# OneSLiPoCharger.net
KiCad netlist of a schematic drawn in EAGLE
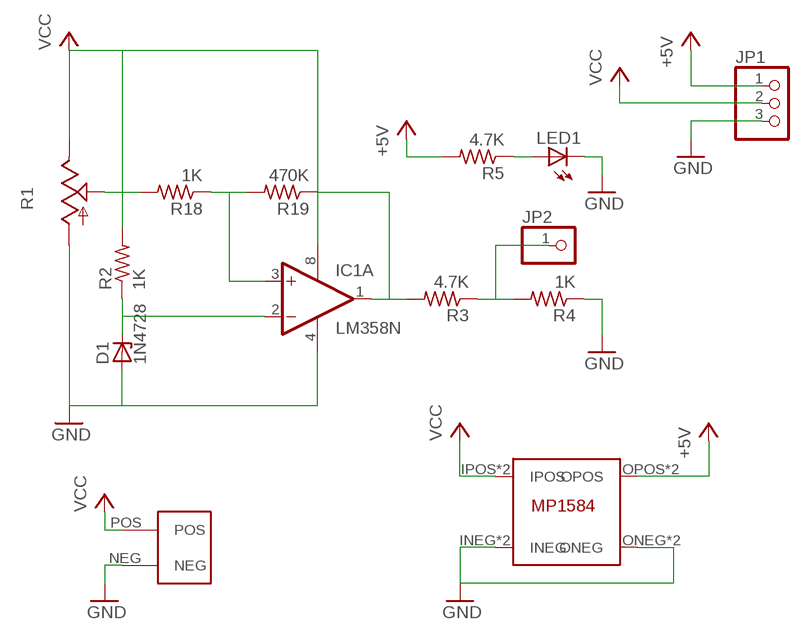
[diagram p0: schematic, sheet 1]
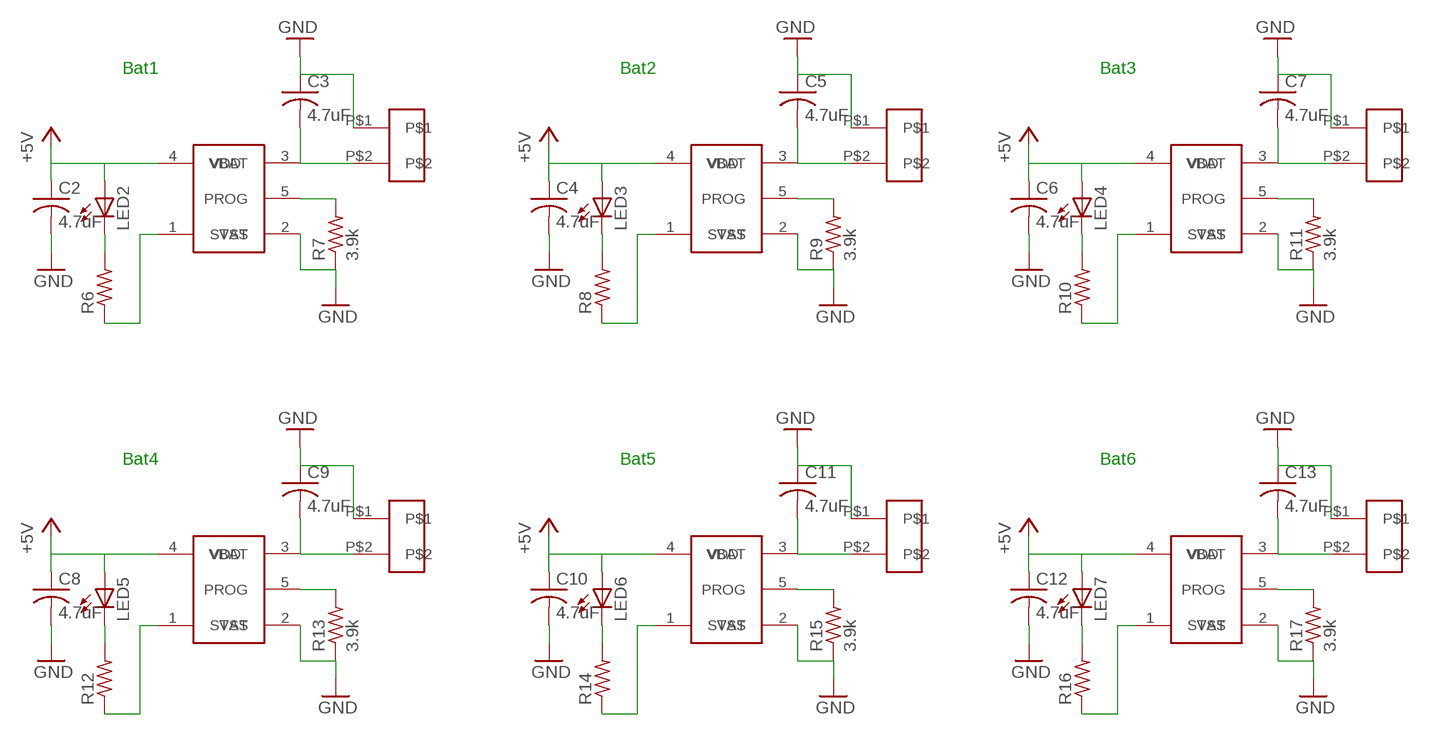
[diagram p1: schematic, sheet 2]

(export (version "E")
  (design (tool "Eeschema 10.0.6"))
  (components
    (comp (ref "D1")
      (value "1N4728")
      (footprint "eagle-import:DO41Z10")
      (libsource (lib "eagle-import") (part "1N4728"))
    )
    (comp (ref "IC1")
      (value "LM358N")
      (footprint "eagle-import:DIL08")
      (libsource (lib "eagle-import") (part "LM358N"))
    )
    (comp (ref "JP1")
      (value "PINHD-1X3")
      (footprint "eagle-import:1X03")
      (libsource (lib "eagle-import") (part "PINHD-1X3"))
    )
    (comp (ref "JP2")
      (value "PINHD-1X1")
      (footprint "eagle-import:1X01")
      (libsource (lib "eagle-import") (part "PINHD-1X1"))
    )
    (comp (ref "LED1")
      (value "LED3MM")
      (footprint "eagle-import:LED3MM")
      (libsource (lib "eagle-import") (part "LED3MM"))
    )
    (comp (ref "R1")
      (value "TRIM_US-B25P")
      (footprint "eagle-import:B25P")
      (libsource (lib "eagle-import") (part "TRIM_US-B25P"))
    )
    (comp (ref "R2")
      (value "1K")
      (footprint "eagle-import:0207_10")
      (libsource (lib "eagle-import") (part "R-US_0207/10"))
    )
    (comp (ref "R3")
      (value "4.7K")
      (footprint "eagle-import:0207_10")
      (libsource (lib "eagle-import") (part "R-US_0207/10"))
    )
    (comp (ref "R4")
      (value "1K")
      (footprint "eagle-import:0207_10")
      (libsource (lib "eagle-import") (part "R-US_0207/10"))
    )
    (comp (ref "R5")
      (value "4.7K")
      (footprint "eagle-import:0207_10")
      (libsource (lib "eagle-import") (part "R-US_0207/10"))
    )
    (comp (ref "R18")
      (value "1K")
      (footprint "eagle-import:0207_10")
      (libsource (lib "eagle-import") (part "R-US_0207/10"))
    )
    (comp (ref "R19")
      (value "470K")
      (footprint "eagle-import:0207_10")
      (libsource (lib "eagle-import") (part "R-US_0207/10"))
    )
    (comp (ref "U$3")
      (value "XT60")
      (footprint "eagle-import:XT60")
      (libsource (lib "eagle-import") (part "XT60"))
    )
    (comp (ref "U$14")
      (value "MP1584EN-MOD")
      (footprint "eagle-import:MP1584MOD-TH")
      (libsource (lib "eagle-import") (part "MP1584EN-MOD"))
    )
    (comp (ref "C2")
      (value "4.7uF")
      (footprint "eagle-import:C0805")
      (libsource (lib "eagle-import") (part "C-USC0805"))
    )
    (comp (ref "C3")
      (value "4.7uF")
      (footprint "eagle-import:C0805")
      (libsource (lib "eagle-import") (part "C-USC0805"))
    )
    (comp (ref "C4")
      (value "4.7uF")
      (footprint "eagle-import:C0805")
      (libsource (lib "eagle-import") (part "C-USC0805"))
    )
    (comp (ref "C5")
      (value "4.7uF")
      (footprint "eagle-import:C0805")
      (libsource (lib "eagle-import") (part "C-USC0805"))
    )
    (comp (ref "C6")
      (value "4.7uF")
      (footprint "eagle-import:C0805")
      (libsource (lib "eagle-import") (part "C-USC0805"))
    )
    (comp (ref "C7")
      (value "4.7uF")
      (footprint "eagle-import:C0805")
      (libsource (lib "eagle-import") (part "C-USC0805"))
    )
    (comp (ref "C8")
      (value "4.7uF")
      (footprint "eagle-import:C0805")
      (libsource (lib "eagle-import") (part "C-USC0805"))
    )
    (comp (ref "C9")
      (value "4.7uF")
      (footprint "eagle-import:C0805")
      (libsource (lib "eagle-import") (part "C-USC0805"))
    )
    (comp (ref "C10")
      (value "4.7uF")
      (footprint "eagle-import:C0805")
      (libsource (lib "eagle-import") (part "C-USC0805"))
    )
    (comp (ref "C11")
      (value "4.7uF")
      (footprint "eagle-import:C0805")
      (libsource (lib "eagle-import") (part "C-USC0805"))
    )
    (comp (ref "C12")
      (value "4.7uF")
      (footprint "eagle-import:C0805")
      (libsource (lib "eagle-import") (part "C-USC0805"))
    )
    (comp (ref "C13")
      (value "4.7uF")
      (footprint "eagle-import:C0805")
      (libsource (lib "eagle-import") (part "C-USC0805"))
    )
    (comp (ref "LED2")
      (value "LED3MM")
      (footprint "eagle-import:LED3MM")
      (libsource (lib "eagle-import") (part "LED3MM"))
    )
    (comp (ref "LED3")
      (value "LED3MM")
      (footprint "eagle-import:LED3MM")
      (libsource (lib "eagle-import") (part "LED3MM"))
    )
    (comp (ref "LED4")
      (value "LED3MM")
      (footprint "eagle-import:LED3MM")
      (libsource (lib "eagle-import") (part "LED3MM"))
    )
    (comp (ref "LED5")
      (value "LED3MM")
      (footprint "eagle-import:LED3MM")
      (libsource (lib "eagle-import") (part "LED3MM"))
    )
    (comp (ref "LED6")
      (value "LED3MM")
      (footprint "eagle-import:LED3MM")
      (libsource (lib "eagle-import") (part "LED3MM"))
    )
    (comp (ref "LED7")
      (value "LED3MM")
      (footprint "eagle-import:LED3MM")
      (libsource (lib "eagle-import") (part "LED3MM"))
    )
    (comp (ref "R6")
      (value "R-US_M0805")
      (footprint "eagle-import:M0805")
      (libsource (lib "eagle-import") (part "R-US_M0805"))
    )
    (comp (ref "R7")
      (value "3.9k")
      (footprint "eagle-import:M0805")
      (libsource (lib "eagle-import") (part "R-US_M0805"))
    )
    (comp (ref "R8")
      (value "R-US_M0805")
      (footprint "eagle-import:M0805")
      (libsource (lib "eagle-import") (part "R-US_M0805"))
    )
    (comp (ref "R9")
      (value "3.9k")
      (footprint "eagle-import:M0805")
      (libsource (lib "eagle-import") (part "R-US_M0805"))
    )
    (comp (ref "R10")
      (value "R-US_M0805")
      (footprint "eagle-import:M0805")
      (libsource (lib "eagle-import") (part "R-US_M0805"))
    )
    (comp (ref "R11")
      (value "3.9k")
      (footprint "eagle-import:M0805")
      (libsource (lib "eagle-import") (part "R-US_M0805"))
    )
    (comp (ref "R12")
      (value "R-US_M0805")
      (footprint "eagle-import:M0805")
      (libsource (lib "eagle-import") (part "R-US_M0805"))
    )
    (comp (ref "R13")
      (value "3.9k")
      (footprint "eagle-import:M0805")
      (libsource (lib "eagle-import") (part "R-US_M0805"))
    )
    (comp (ref "R14")
      (value "R-US_M0805")
      (footprint "eagle-import:M0805")
      (libsource (lib "eagle-import") (part "R-US_M0805"))
    )
    (comp (ref "R15")
      (value "3.9k")
      (footprint "eagle-import:M0805")
      (libsource (lib "eagle-import") (part "R-US_M0805"))
    )
    (comp (ref "R16")
      (value "R-US_M0805")
      (footprint "eagle-import:M0805")
      (libsource (lib "eagle-import") (part "R-US_M0805"))
    )
    (comp (ref "R17")
      (value "3.9k")
      (footprint "eagle-import:M0805")
      (libsource (lib "eagle-import") (part "R-US_M0805"))
    )
    (comp (ref "U$1")
      (value "MCP73831")
      (footprint "eagle-import:MCP73831-SOT23")
      (libsource (lib "eagle-import") (part "MCP73831"))
    )
    (comp (ref "U$2")
      (value "PICOBLADE-2PIN")
      (footprint "eagle-import:PICOBLADE-2PIN")
      (libsource (lib "eagle-import") (part "PICOBLADE-2PIN"))
    )
    (comp (ref "U$4")
      (value "MCP73831")
      (footprint "eagle-import:MCP73831-SOT23")
      (libsource (lib "eagle-import") (part "MCP73831"))
    )
    (comp (ref "U$5")
      (value "PICOBLADE-2PIN")
      (footprint "eagle-import:PICOBLADE-2PIN")
      (libsource (lib "eagle-import") (part "PICOBLADE-2PIN"))
    )
    (comp (ref "U$6")
      (value "MCP73831")
      (footprint "eagle-import:MCP73831-SOT23")
      (libsource (lib "eagle-import") (part "MCP73831"))
    )
    (comp (ref "U$7")
      (value "PICOBLADE-2PIN")
      (footprint "eagle-import:PICOBLADE-2PIN")
      (libsource (lib "eagle-import") (part "PICOBLADE-2PIN"))
    )
    (comp (ref "U$8")
      (value "MCP73831")
      (footprint "eagle-import:MCP73831-SOT23")
      (libsource (lib "eagle-import") (part "MCP73831"))
    )
    (comp (ref "U$9")
      (value "PICOBLADE-2PIN")
      (footprint "eagle-import:PICOBLADE-2PIN")
      (libsource (lib "eagle-import") (part "PICOBLADE-2PIN"))
    )
    (comp (ref "U$10")
      (value "MCP73831")
      (footprint "eagle-import:MCP73831-SOT23")
      (libsource (lib "eagle-import") (part "MCP73831"))
    )
    (comp (ref "U$11")
      (value "PICOBLADE-2PIN")
      (footprint "eagle-import:PICOBLADE-2PIN")
      (libsource (lib "eagle-import") (part "PICOBLADE-2PIN"))
    )
    (comp (ref "U$12")
      (value "MCP73831")
      (footprint "eagle-import:MCP73831-SOT23")
      (libsource (lib "eagle-import") (part "MCP73831"))
    )
    (comp (ref "U$13")
      (value "PICOBLADE-2PIN")
      (footprint "eagle-import:PICOBLADE-2PIN")
      (libsource (lib "eagle-import") (part "PICOBLADE-2PIN"))
    )
  )
  (nets
    (net (code "1") (name "+5V") (class "Default")
      (node (ref "C10") (pin "1") (pinfunction "1_1") (pintype "passive"))
      (node (ref "C12") (pin "1") (pinfunction "1_1") (pintype "passive"))
      (node (ref "C2") (pin "1") (pinfunction "1_1") (pintype "passive"))
      (node (ref "C4") (pin "1") (pinfunction "1_1") (pintype "passive"))
      (node (ref "C6") (pin "1") (pinfunction "1_1") (pintype "passive"))
      (node (ref "C8") (pin "1") (pinfunction "1_1") (pintype "passive"))
      (node (ref "JP1") (pin "1") (pinfunction "1_1") (pintype "passive"))
      (node (ref "LED2") (pin "A") (pinfunction "A_A") (pintype "passive"))
      (node (ref "LED3") (pin "A") (pinfunction "A_A") (pintype "passive"))
      (node (ref "LED4") (pin "A") (pinfunction "A_A") (pintype "passive"))
      (node (ref "LED5") (pin "A") (pinfunction "A_A") (pintype "passive"))
      (node (ref "LED6") (pin "A") (pinfunction "A_A") (pintype "passive"))
      (node (ref "LED7") (pin "A") (pinfunction "A_A") (pintype "passive"))
      (node (ref "R5") (pin "2") (pinfunction "2_2") (pintype "passive"))
      (node (ref "U$1") (pin "4") (pinfunction "VDD_4") (pintype "bidirectional"))
      (node (ref "U$10") (pin "4") (pinfunction "VDD_4") (pintype "bidirectional"))
      (node (ref "U$12") (pin "4") (pinfunction "VDD_4") (pintype "bidirectional"))
      (node (ref "U$14") (pin "OPOS") (pinfunction "OPOS_OPOS") (pintype "bidirectional"))
      (node (ref "U$14") (pin "OPOS1") (pinfunction "OPOS_OPOS1") (pintype "bidirectional"))
      (node (ref "U$4") (pin "4") (pinfunction "VDD_4") (pintype "bidirectional"))
      (node (ref "U$6") (pin "4") (pinfunction "VDD_4") (pintype "bidirectional"))
      (node (ref "U$8") (pin "4") (pinfunction "VDD_4") (pintype "bidirectional"))
    )
    (net (code "2") (name "GND") (class "Default")
      (node (ref "C10") (pin "2") (pinfunction "2_2") (pintype "passive"))
      (node (ref "C11") (pin "1") (pinfunction "1_1") (pintype "passive"))
      (node (ref "C12") (pin "2") (pinfunction "2_2") (pintype "passive"))
      (node (ref "C13") (pin "1") (pinfunction "1_1") (pintype "passive"))
      (node (ref "C2") (pin "2") (pinfunction "2_2") (pintype "passive"))
      (node (ref "C3") (pin "1") (pinfunction "1_1") (pintype "passive"))
      (node (ref "C4") (pin "2") (pinfunction "2_2") (pintype "passive"))
      (node (ref "C5") (pin "1") (pinfunction "1_1") (pintype "passive"))
      (node (ref "C6") (pin "2") (pinfunction "2_2") (pintype "passive"))
      (node (ref "C7") (pin "1") (pinfunction "1_1") (pintype "passive"))
      (node (ref "C8") (pin "2") (pinfunction "2_2") (pintype "passive"))
      (node (ref "C9") (pin "1") (pinfunction "1_1") (pintype "passive"))
      (node (ref "D1") (pin "A") (pinfunction "A_A") (pintype "passive"))
      (node (ref "IC1") (pin "4") (pinfunction "V-_4") (pintype "power_in"))
      (node (ref "JP1") (pin "3") (pinfunction "3_3") (pintype "passive"))
      (node (ref "LED1") (pin "K") (pinfunction "C_K") (pintype "passive"))
      (node (ref "R1") (pin "A") (pinfunction "A_A") (pintype "passive"))
      (node (ref "R11") (pin "1") (pinfunction "1_1") (pintype "passive"))
      (node (ref "R13") (pin "1") (pinfunction "1_1") (pintype "passive"))
      (node (ref "R15") (pin "1") (pinfunction "1_1") (pintype "passive"))
      (node (ref "R17") (pin "1") (pinfunction "1_1") (pintype "passive"))
      (node (ref "R4") (pin "1") (pinfunction "1_1") (pintype "passive"))
      (node (ref "R7") (pin "1") (pinfunction "1_1") (pintype "passive"))
      (node (ref "R9") (pin "1") (pinfunction "1_1") (pintype "passive"))
      (node (ref "U$1") (pin "2") (pinfunction "VSS_2") (pintype "bidirectional"))
      (node (ref "U$10") (pin "2") (pinfunction "VSS_2") (pintype "bidirectional"))
      (node (ref "U$11") (pin "P$1") (pinfunction "P$1_P$1") (pintype "bidirectional"))
      (node (ref "U$12") (pin "2") (pinfunction "VSS_2") (pintype "bidirectional"))
      (node (ref "U$13") (pin "P$1") (pinfunction "P$1_P$1") (pintype "bidirectional"))
      (node (ref "U$14") (pin "INEG") (pinfunction "INEG_INEG") (pintype "bidirectional"))
      (node (ref "U$14") (pin "INEG1") (pinfunction "INEG_INEG1") (pintype "bidirectional"))
      (node (ref "U$14") (pin "ONEG") (pinfunction "ONEG_ONEG") (pintype "bidirectional"))
      (node (ref "U$14") (pin "ONEG1") (pinfunction "ONEG_ONEG1") (pintype "bidirectional"))
      (node (ref "U$2") (pin "P$1") (pinfunction "P$1_P$1") (pintype "bidirectional"))
      (node (ref "U$3") (pin "NEG") (pinfunction "NEG_NEG") (pintype "bidirectional"))
      (node (ref "U$4") (pin "2") (pinfunction "VSS_2") (pintype "bidirectional"))
      (node (ref "U$5") (pin "P$1") (pinfunction "P$1_P$1") (pintype "bidirectional"))
      (node (ref "U$6") (pin "2") (pinfunction "VSS_2") (pintype "bidirectional"))
      (node (ref "U$7") (pin "P$1") (pinfunction "P$1_P$1") (pintype "bidirectional"))
      (node (ref "U$8") (pin "2") (pinfunction "VSS_2") (pintype "bidirectional"))
      (node (ref "U$9") (pin "P$1") (pinfunction "P$1_P$1") (pintype "bidirectional"))
    )
    (net (code "3") (name "Net-(IC1A-+IN)") (class "Default")
      (node (ref "IC1") (pin "3") (pinfunction "+IN_3") (pintype "input"))
      (node (ref "R18") (pin "1") (pinfunction "1_1") (pintype "passive"))
      (node (ref "R19") (pin "2") (pinfunction "2_2") (pintype "passive"))
    )
    (net (code "4") (name "Net-(IC1A--IN)") (class "Default")
      (node (ref "D1") (pin "C") (pinfunction "C_C") (pintype "passive"))
      (node (ref "IC1") (pin "2") (pinfunction "-IN_2") (pintype "input"))
      (node (ref "R2") (pin "1") (pinfunction "1_1") (pintype "passive"))
    )
    (net (code "5") (name "Net-(IC1A-OUT)") (class "Default")
      (node (ref "IC1") (pin "1") (pinfunction "OUT_1") (pintype "output"))
      (node (ref "R19") (pin "1") (pinfunction "1_1") (pintype "passive"))
      (node (ref "R3") (pin "2") (pinfunction "2_2") (pintype "passive"))
    )
    (net (code "6") (name "Net-(JP2-Pad1)") (class "Default")
      (node (ref "JP2") (pin "1") (pinfunction "1_1") (pintype "passive"))
      (node (ref "R3") (pin "1") (pinfunction "1_1") (pintype "passive"))
      (node (ref "R4") (pin "2") (pinfunction "2_2") (pintype "passive"))
    )
    (net (code "7") (name "Net-(LED1-PadA)") (class "Default")
      (node (ref "LED1") (pin "A") (pinfunction "A_A") (pintype "passive"))
      (node (ref "R5") (pin "1") (pinfunction "1_1") (pintype "passive"))
    )
    (net (code "8") (name "Net-(LED2-C)") (class "Default")
      (node (ref "LED2") (pin "K") (pinfunction "C_K") (pintype "passive"))
      (node (ref "R6") (pin "2") (pinfunction "2_2") (pintype "passive"))
    )
    (net (code "9") (name "Net-(LED3-C)") (class "Default")
      (node (ref "LED3") (pin "K") (pinfunction "C_K") (pintype "passive"))
      (node (ref "R8") (pin "2") (pinfunction "2_2") (pintype "passive"))
    )
    (net (code "10") (name "Net-(LED4-C)") (class "Default")
      (node (ref "LED4") (pin "K") (pinfunction "C_K") (pintype "passive"))
      (node (ref "R10") (pin "2") (pinfunction "2_2") (pintype "passive"))
    )
    (net (code "11") (name "Net-(LED5-C)") (class "Default")
      (node (ref "LED5") (pin "K") (pinfunction "C_K") (pintype "passive"))
      (node (ref "R12") (pin "2") (pinfunction "2_2") (pintype "passive"))
    )
    (net (code "12") (name "Net-(LED6-C)") (class "Default")
      (node (ref "LED6") (pin "K") (pinfunction "C_K") (pintype "passive"))
      (node (ref "R14") (pin "2") (pinfunction "2_2") (pintype "passive"))
    )
    (net (code "13") (name "Net-(LED7-C)") (class "Default")
      (node (ref "LED7") (pin "K") (pinfunction "C_K") (pintype "passive"))
      (node (ref "R16") (pin "2") (pinfunction "2_2") (pintype "passive"))
    )
    (net (code "14") (name "Net-(R1-PadS)") (class "Default")
      (node (ref "R1") (pin "S") (pinfunction "S_S") (pintype "passive"))
      (node (ref "R18") (pin "2") (pinfunction "2_2") (pintype "passive"))
    )
    (net (code "15") (name "Net-(U$1-PROG)") (class "Default")
      (node (ref "R7") (pin "2") (pinfunction "2_2") (pintype "passive"))
      (node (ref "U$1") (pin "5") (pinfunction "PROG_5") (pintype "bidirectional"))
    )
    (net (code "16") (name "Net-(U$1-STAT)") (class "Default")
      (node (ref "R6") (pin "1") (pinfunction "1_1") (pintype "passive"))
      (node (ref "U$1") (pin "1") (pinfunction "STAT_1") (pintype "bidirectional"))
    )
    (net (code "17") (name "Net-(U$1-VBAT)") (class "Default")
      (node (ref "C3") (pin "2") (pinfunction "2_2") (pintype "passive"))
      (node (ref "U$1") (pin "3") (pinfunction "VBAT_3") (pintype "bidirectional"))
      (node (ref "U$2") (pin "P$2") (pinfunction "P$2_P$2") (pintype "bidirectional"))
    )
    (net (code "18") (name "Net-(U$4-PROG)") (class "Default")
      (node (ref "R9") (pin "2") (pinfunction "2_2") (pintype "passive"))
      (node (ref "U$4") (pin "5") (pinfunction "PROG_5") (pintype "bidirectional"))
    )
    (net (code "19") (name "Net-(U$4-STAT)") (class "Default")
      (node (ref "R8") (pin "1") (pinfunction "1_1") (pintype "passive"))
      (node (ref "U$4") (pin "1") (pinfunction "STAT_1") (pintype "bidirectional"))
    )
    (net (code "20") (name "Net-(U$4-VBAT)") (class "Default")
      (node (ref "C5") (pin "2") (pinfunction "2_2") (pintype "passive"))
      (node (ref "U$4") (pin "3") (pinfunction "VBAT_3") (pintype "bidirectional"))
      (node (ref "U$5") (pin "P$2") (pinfunction "P$2_P$2") (pintype "bidirectional"))
    )
    (net (code "21") (name "Net-(U$6-PROG)") (class "Default")
      (node (ref "R11") (pin "2") (pinfunction "2_2") (pintype "passive"))
      (node (ref "U$6") (pin "5") (pinfunction "PROG_5") (pintype "bidirectional"))
    )
    (net (code "22") (name "Net-(U$6-STAT)") (class "Default")
      (node (ref "R10") (pin "1") (pinfunction "1_1") (pintype "passive"))
      (node (ref "U$6") (pin "1") (pinfunction "STAT_1") (pintype "bidirectional"))
    )
    (net (code "23") (name "Net-(U$6-VBAT)") (class "Default")
      (node (ref "C7") (pin "2") (pinfunction "2_2") (pintype "passive"))
      (node (ref "U$6") (pin "3") (pinfunction "VBAT_3") (pintype "bidirectional"))
      (node (ref "U$7") (pin "P$2") (pinfunction "P$2_P$2") (pintype "bidirectional"))
    )
    (net (code "24") (name "Net-(U$8-PROG)") (class "Default")
      (node (ref "R13") (pin "2") (pinfunction "2_2") (pintype "passive"))
      (node (ref "U$8") (pin "5") (pinfunction "PROG_5") (pintype "bidirectional"))
    )
    (net (code "25") (name "Net-(U$8-STAT)") (class "Default")
      (node (ref "R12") (pin "1") (pinfunction "1_1") (pintype "passive"))
      (node (ref "U$8") (pin "1") (pinfunction "STAT_1") (pintype "bidirectional"))
    )
    (net (code "26") (name "Net-(U$8-VBAT)") (class "Default")
      (node (ref "C9") (pin "2") (pinfunction "2_2") (pintype "passive"))
      (node (ref "U$8") (pin "3") (pinfunction "VBAT_3") (pintype "bidirectional"))
      (node (ref "U$9") (pin "P$2") (pinfunction "P$2_P$2") (pintype "bidirectional"))
    )
    (net (code "27") (name "Net-(U$10-PROG)") (class "Default")
      (node (ref "R15") (pin "2") (pinfunction "2_2") (pintype "passive"))
      (node (ref "U$10") (pin "5") (pinfunction "PROG_5") (pintype "bidirectional"))
    )
    (net (code "28") (name "Net-(U$10-STAT)") (class "Default")
      (node (ref "R14") (pin "1") (pinfunction "1_1") (pintype "passive"))
      (node (ref "U$10") (pin "1") (pinfunction "STAT_1") (pintype "bidirectional"))
    )
    (net (code "29") (name "Net-(U$10-VBAT)") (class "Default")
      (node (ref "C11") (pin "2") (pinfunction "2_2") (pintype "passive"))
      (node (ref "U$10") (pin "3") (pinfunction "VBAT_3") (pintype "bidirectional"))
      (node (ref "U$11") (pin "P$2") (pinfunction "P$2_P$2") (pintype "bidirectional"))
    )
    (net (code "30") (name "Net-(U$12-PROG)") (class "Default")
      (node (ref "R17") (pin "2") (pinfunction "2_2") (pintype "passive"))
      (node (ref "U$12") (pin "5") (pinfunction "PROG_5") (pintype "bidirectional"))
    )
    (net (code "31") (name "Net-(U$12-STAT)") (class "Default")
      (node (ref "R16") (pin "1") (pinfunction "1_1") (pintype "passive"))
      (node (ref "U$12") (pin "1") (pinfunction "STAT_1") (pintype "bidirectional"))
    )
    (net (code "32") (name "Net-(U$12-VBAT)") (class "Default")
      (node (ref "C13") (pin "2") (pinfunction "2_2") (pintype "passive"))
      (node (ref "U$12") (pin "3") (pinfunction "VBAT_3") (pintype "bidirectional"))
      (node (ref "U$13") (pin "P$2") (pinfunction "P$2_P$2") (pintype "bidirectional"))
    )
    (net (code "33") (name "VCC") (class "Default")
      (node (ref "IC1") (pin "8") (pinfunction "V+_8") (pintype "power_in"))
      (node (ref "JP1") (pin "2") (pinfunction "2_2") (pintype "passive"))
      (node (ref "R1") (pin "E") (pinfunction "E_E") (pintype "passive"))
      (node (ref "R2") (pin "2") (pinfunction "2_2") (pintype "passive"))
      (node (ref "U$14") (pin "IPOS") (pinfunction "IPOS_IPOS") (pintype "bidirectional"))
      (node (ref "U$14") (pin "IPOS1") (pinfunction "IPOS_IPOS1") (pintype "bidirectional"))
      (node (ref "U$3") (pin "POS") (pinfunction "POS_POS") (pintype "bidirectional"))
    )
  )
)
